# MCMP_Projeto_Final.net
KiCad netlist of a schematic drawn in EAGLE
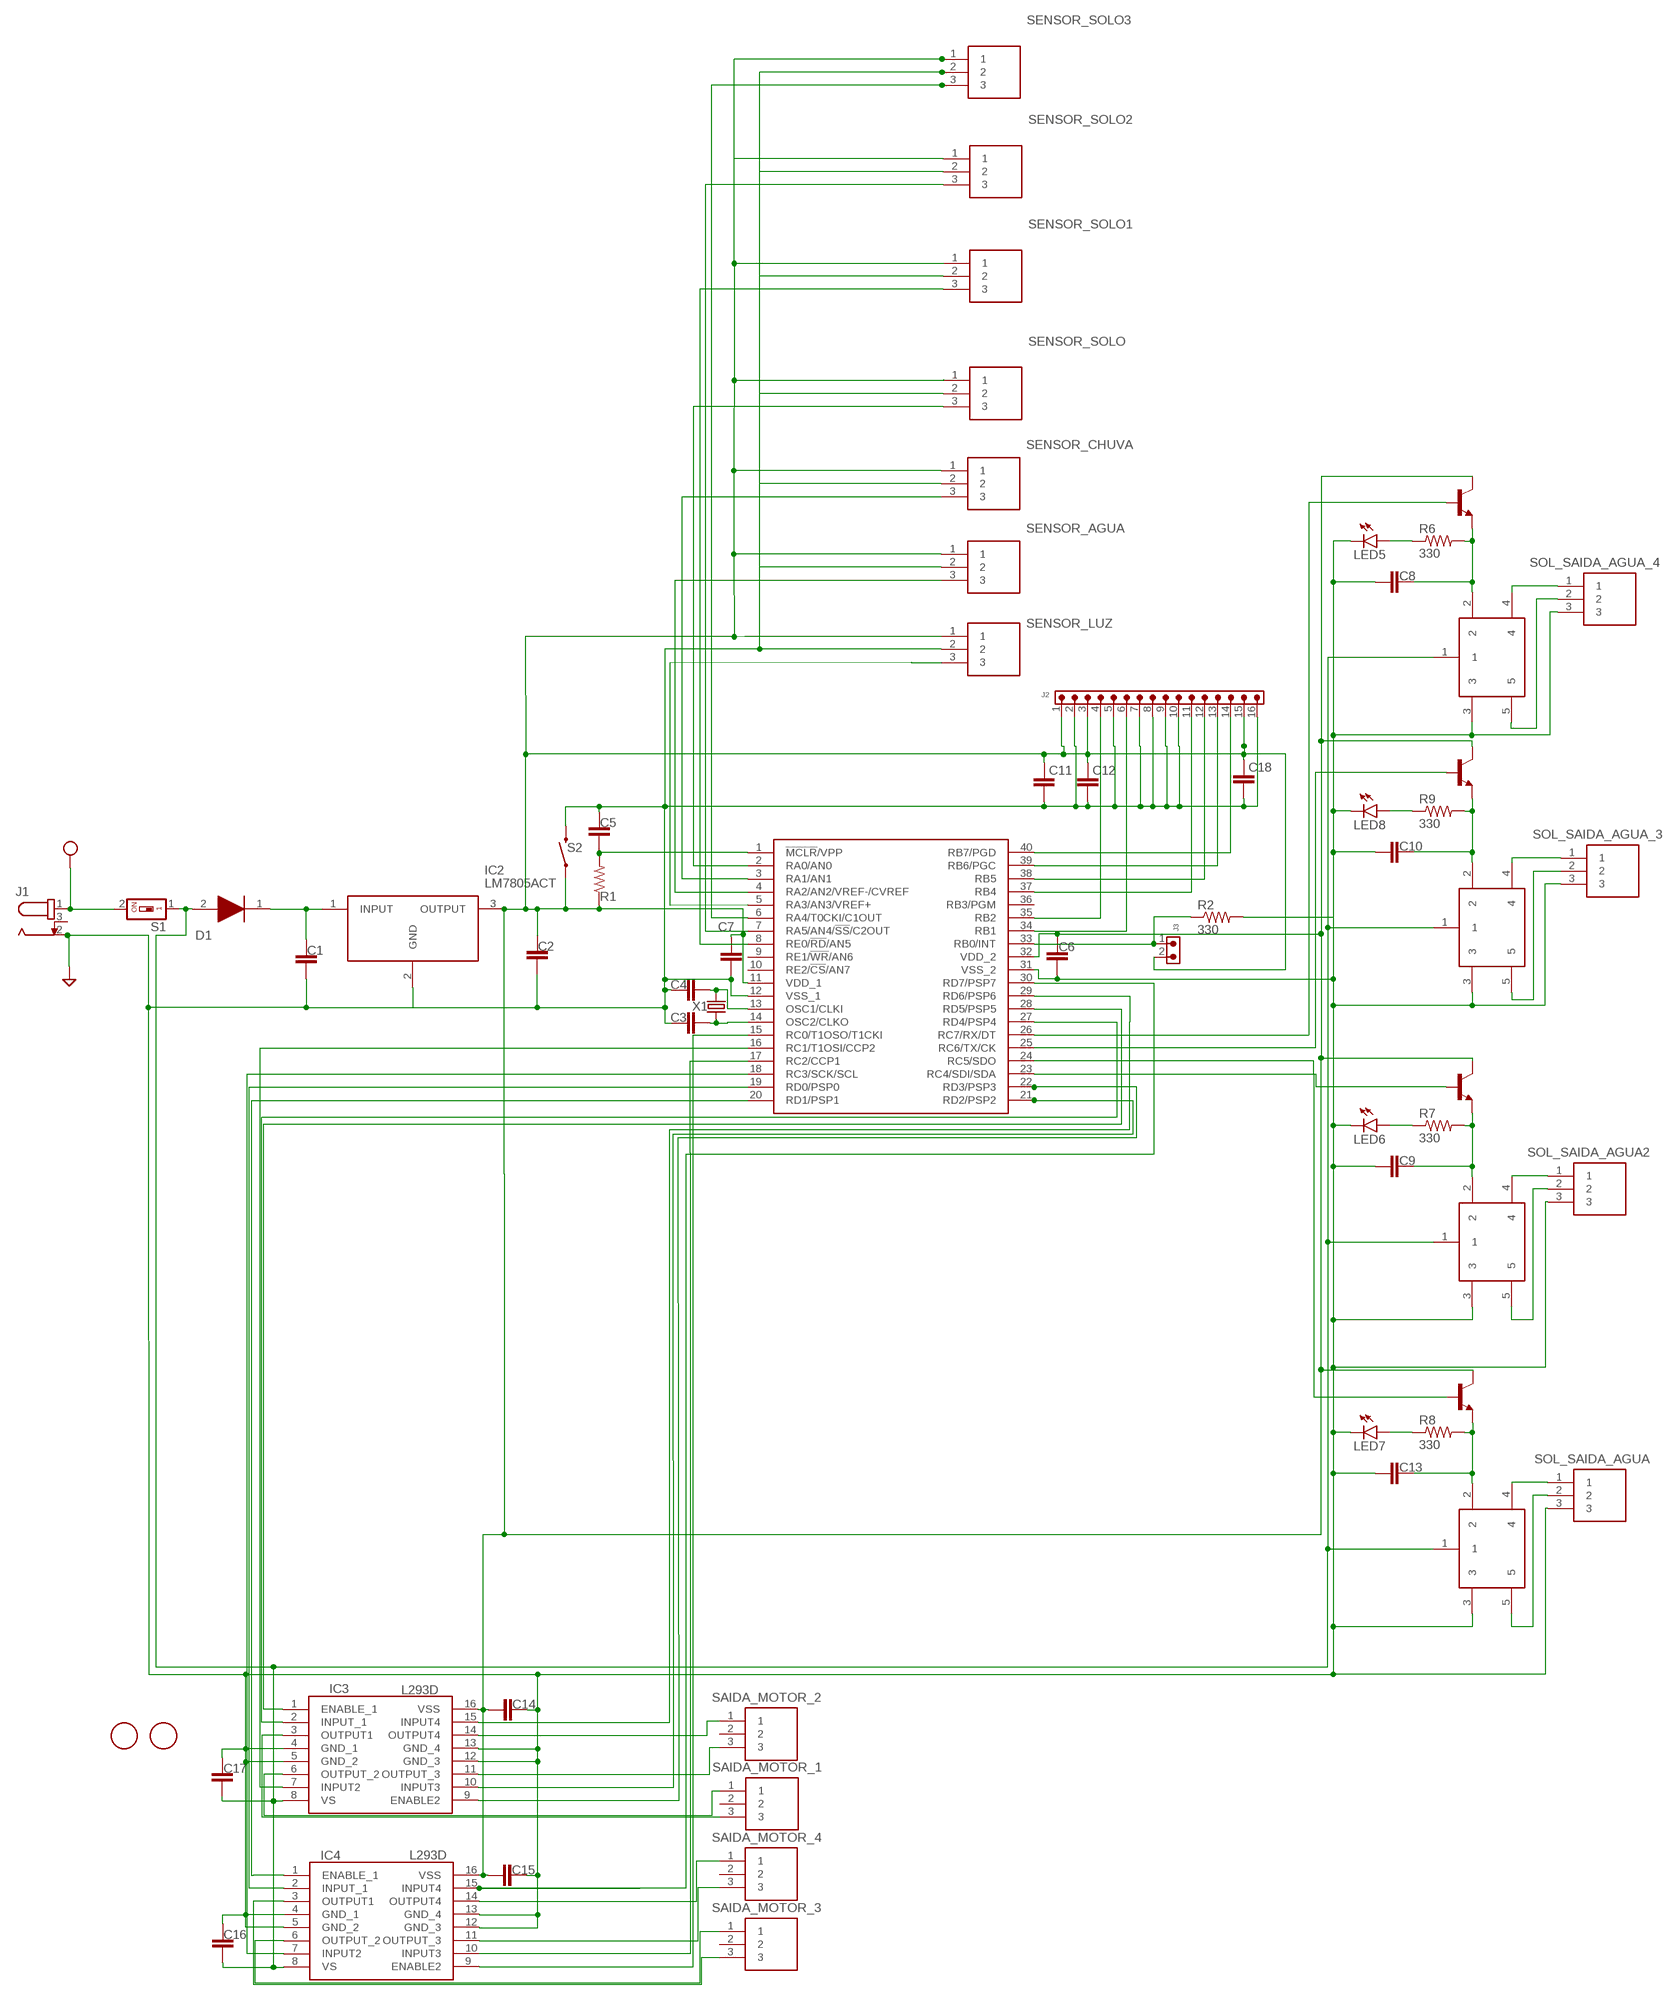
[diagram p0: schematic, sheet 1]

(export (version "E")
  (design (tool "Eeschema 10.0.6"))
  (components
    (comp (ref "C1")
      (value "470uF")
      (footprint "eagle-import:CAP_0805")
      (fields
        (field (name "DIGIKEY_PART_NUMBER") "311-1140-2-ND")
        (field (name "MANUFACTURER") "Yageo")
        (field (name "MPN") "CC0805KRX7R9BB104")
        (field (name "CREATED_BY") "PCBLayout.com")
      )
      (libsource (lib "eagle-import") (part "CC0805KRX7R9BB104"))
    )
    (comp (ref "C2")
      (value "1uF")
      (footprint "eagle-import:CAP_0805")
      (fields
        (field (name "DIGIKEY_PART_NUMBER") "311-1140-2-ND")
        (field (name "MANUFACTURER") "Yageo")
        (field (name "MPN") "CC0805KRX7R9BB104")
        (field (name "CREATED_BY") "PCBLayout.com")
      )
      (libsource (lib "eagle-import") (part "CC0805KRX7R9BB104"))
    )
    (comp (ref "C3")
      (value "33p")
      (footprint "eagle-import:CAP_0805")
      (fields
        (field (name "DIGIKEY_PART_NUMBER") "311-1140-2-ND")
        (field (name "MANUFACTURER") "Yageo")
        (field (name "MPN") "CC0805KRX7R9BB104")
        (field (name "CREATED_BY") "PCBLayout.com")
      )
      (libsource (lib "eagle-import") (part "CC0805KRX7R9BB104"))
    )
    (comp (ref "C4")
      (value "33p")
      (footprint "eagle-import:CAP_0805")
      (fields
        (field (name "DIGIKEY_PART_NUMBER") "311-1140-2-ND")
        (field (name "MANUFACTURER") "Yageo")
        (field (name "MPN") "CC0805KRX7R9BB104")
        (field (name "CREATED_BY") "PCBLayout.com")
      )
      (libsource (lib "eagle-import") (part "CC0805KRX7R9BB104"))
    )
    (comp (ref "C5")
      (value "10u")
      (footprint "eagle-import:CAP_0805")
      (fields
        (field (name "DIGIKEY_PART_NUMBER") "311-1140-2-ND")
        (field (name "MANUFACTURER") "Yageo")
        (field (name "MPN") "CC0805KRX7R9BB104")
        (field (name "CREATED_BY") "PCBLayout.com")
      )
      (libsource (lib "eagle-import") (part "CC0805KRX7R9BB104"))
    )
    (comp (ref "C6")
      (value "10u")
      (footprint "eagle-import:CAP_0805")
      (fields
        (field (name "DIGIKEY_PART_NUMBER") "311-1140-2-ND")
        (field (name "MANUFACTURER") "Yageo")
        (field (name "MPN") "CC0805KRX7R9BB104")
        (field (name "CREATED_BY") "PCBLayout.com")
      )
      (libsource (lib "eagle-import") (part "CC0805KRX7R9BB104"))
    )
    (comp (ref "C7")
      (value "10u")
      (footprint "eagle-import:CAP_0805")
      (fields
        (field (name "DIGIKEY_PART_NUMBER") "311-1140-2-ND")
        (field (name "MANUFACTURER") "Yageo")
        (field (name "MPN") "CC0805KRX7R9BB104")
        (field (name "CREATED_BY") "PCBLayout.com")
      )
      (libsource (lib "eagle-import") (part "CC0805KRX7R9BB104"))
    )
    (comp (ref "C8")
      (value "10u")
      (footprint "eagle-import:CAP_0805")
      (fields
        (field (name "DIGIKEY_PART_NUMBER") "311-1140-2-ND")
        (field (name "MANUFACTURER") "Yageo")
        (field (name "MPN") "CC0805KRX7R9BB104")
        (field (name "CREATED_BY") "PCBLayout.com")
      )
      (libsource (lib "eagle-import") (part "CC0805KRX7R9BB104"))
    )
    (comp (ref "C9")
      (value "10u")
      (footprint "eagle-import:CAP_0805")
      (fields
        (field (name "DIGIKEY_PART_NUMBER") "311-1140-2-ND")
        (field (name "MANUFACTURER") "Yageo")
        (field (name "MPN") "CC0805KRX7R9BB104")
        (field (name "CREATED_BY") "PCBLayout.com")
      )
      (libsource (lib "eagle-import") (part "CC0805KRX7R9BB104"))
    )
    (comp (ref "C10")
      (value "10u")
      (footprint "eagle-import:CAP_0805")
      (fields
        (field (name "DIGIKEY_PART_NUMBER") "311-1140-2-ND")
        (field (name "MANUFACTURER") "Yageo")
        (field (name "MPN") "CC0805KRX7R9BB104")
        (field (name "CREATED_BY") "PCBLayout.com")
      )
      (libsource (lib "eagle-import") (part "CC0805KRX7R9BB104"))
    )
    (comp (ref "C11")
      (value "10u")
      (footprint "eagle-import:CAP_0805")
      (fields
        (field (name "DIGIKEY_PART_NUMBER") "311-1140-2-ND")
        (field (name "MANUFACTURER") "Yageo")
        (field (name "MPN") "CC0805KRX7R9BB104")
        (field (name "CREATED_BY") "PCBLayout.com")
      )
      (libsource (lib "eagle-import") (part "CC0805KRX7R9BB104"))
    )
    (comp (ref "C12")
      (value "10u")
      (footprint "eagle-import:CAP_0805")
      (fields
        (field (name "DIGIKEY_PART_NUMBER") "311-1140-2-ND")
        (field (name "MANUFACTURER") "Yageo")
        (field (name "MPN") "CC0805KRX7R9BB104")
        (field (name "CREATED_BY") "PCBLayout.com")
      )
      (libsource (lib "eagle-import") (part "CC0805KRX7R9BB104"))
    )
    (comp (ref "C13")
      (value "10u")
      (footprint "eagle-import:CAP_0805")
      (fields
        (field (name "DIGIKEY_PART_NUMBER") "311-1140-2-ND")
        (field (name "MANUFACTURER") "Yageo")
        (field (name "MPN") "CC0805KRX7R9BB104")
        (field (name "CREATED_BY") "PCBLayout.com")
      )
      (libsource (lib "eagle-import") (part "CC0805KRX7R9BB104"))
    )
    (comp (ref "C14")
      (value "0.1u")
      (footprint "eagle-import:CAP_0805")
      (fields
        (field (name "DIGIKEY_PART_NUMBER") "311-1140-2-ND")
        (field (name "MANUFACTURER") "Yageo")
        (field (name "MPN") "CC0805KRX7R9BB104")
        (field (name "CREATED_BY") "PCBLayout.com")
      )
      (libsource (lib "eagle-import") (part "CC0805KRX7R9BB104"))
    )
    (comp (ref "C15")
      (value "0.1u")
      (footprint "eagle-import:CAP_0805")
      (fields
        (field (name "DIGIKEY_PART_NUMBER") "311-1140-2-ND")
        (field (name "MANUFACTURER") "Yageo")
        (field (name "MPN") "CC0805KRX7R9BB104")
        (field (name "CREATED_BY") "PCBLayout.com")
      )
      (libsource (lib "eagle-import") (part "CC0805KRX7R9BB104"))
    )
    (comp (ref "C16")
      (value "100u")
      (footprint "eagle-import:CAP_0805")
      (fields
        (field (name "DIGIKEY_PART_NUMBER") "311-1140-2-ND")
        (field (name "MANUFACTURER") "Yageo")
        (field (name "MPN") "CC0805KRX7R9BB104")
        (field (name "CREATED_BY") "PCBLayout.com")
      )
      (libsource (lib "eagle-import") (part "CC0805KRX7R9BB104"))
    )
    (comp (ref "C17")
      (value "100u")
      (footprint "eagle-import:CAP_0805")
      (fields
        (field (name "DIGIKEY_PART_NUMBER") "311-1140-2-ND")
        (field (name "MANUFACTURER") "Yageo")
        (field (name "MPN") "CC0805KRX7R9BB104")
        (field (name "CREATED_BY") "PCBLayout.com")
      )
      (libsource (lib "eagle-import") (part "CC0805KRX7R9BB104"))
    )
    (comp (ref "C18")
      (value "10u")
      (footprint "eagle-import:CAP_0805")
      (fields
        (field (name "DIGIKEY_PART_NUMBER") "311-1140-2-ND")
        (field (name "MANUFACTURER") "Yageo")
        (field (name "MPN") "CC0805KRX7R9BB104")
        (field (name "CREATED_BY") "PCBLayout.com")
      )
      (libsource (lib "eagle-import") (part "CC0805KRX7R9BB104"))
    )
    (comp (ref "D1")
      (value "1N4007S")
      (footprint "eagle-import:DIOAD1470W65L470D250")
      (fields (field (name "MOUSER_PART_NUMBER") "821-1N4007S"))
      (libsource (lib "eagle-import") (part "1N4007S"))
    )
    (comp (ref "IC1")
      (value "PIC16F877A-I_P")
      (footprint "eagle-import:DIP1550W56P254L5219H483Q40N")
      (fields
        (field (name "ARROW_PART_NUMBER") "PIC16F877A-I/P")
        (field (name "MOUSER_PART_NUMBER") "579-PIC16F877A-I/P")
      )
      (libsource (lib "eagle-import") (part "PIC16F877A-I_P"))
    )
    (comp (ref "IC2")
      (value "LM7805ACT")
      (footprint "eagle-import:TO254P470X1016X2019-3P")
      (fields (field (name "MOUSER_PART_NUMBER") "512-LM7805ACT"))
      (libsource (lib "eagle-import") (part "LM7805ACT"))
    )
    (comp (ref "IC3")
      (value "L293D")
      (footprint "eagle-import:DIP880W50P254L2000H510Q16N")
      (fields (field (name "MOUSER_PART_NUMBER") "511-L293D"))
      (libsource (lib "eagle-import") (part "L293D"))
    )
    (comp (ref "IC4")
      (value "L293D")
      (footprint "eagle-import:DIP880W50P254L2000H510Q16N")
      (fields (field (name "MOUSER_PART_NUMBER") "511-L293D"))
      (libsource (lib "eagle-import") (part "L293D"))
    )
    (comp (ref "J1")
      (value "694106301002")
      (footprint "eagle-import:694106301002")
      (fields
        (field (name "DIGIKEY_PART_NUMBER") "732-5930-ND")
        (field (name "MANUFACTURER") "Wurth Electronics Inc.")
        (field (name "CREATED_BY") "PCBLayout.com")
      )
      (libsource (lib "eagle-import") (part "694106301002"))
    )
    (comp (ref "J2")
      (value "6130XX11121_61301611121")
      (footprint "eagle-import:61301611121")
      (libsource (lib "eagle-import") (part "6130XX11121_61301611121"))
    )
    (comp (ref "J3")
      (value "6200XX11121_62000211121")
      (footprint "eagle-import:62000211121")
      (libsource (lib "eagle-import") (part "6200XX11121_62000211121"))
    )
    (comp (ref "K1")
      (value "SRD-05VDC-SL-C")
      (footprint "eagle-import:SRD")
      (libsource (lib "eagle-import") (part "SRD-05VDC-SL-C"))
    )
    (comp (ref "K2")
      (value "SRD-05VDC-SL-C")
      (footprint "eagle-import:SRD")
      (libsource (lib "eagle-import") (part "SRD-05VDC-SL-C"))
    )
    (comp (ref "K3")
      (value "SRD-05VDC-SL-C")
      (footprint "eagle-import:SRD")
      (libsource (lib "eagle-import") (part "SRD-05VDC-SL-C"))
    )
    (comp (ref "K5")
      (value "SRD-05VDC-SL-C")
      (footprint "eagle-import:SRD")
      (libsource (lib "eagle-import") (part "SRD-05VDC-SL-C"))
    )
    (comp (ref "LED5")
      (value "LEDCHIPLED_0805")
      (footprint "eagle-import:CHIPLED_0805")
      (libsource (lib "eagle-import") (part "LEDCHIPLED_0805"))
    )
    (comp (ref "LED6")
      (value "LEDCHIPLED_0805")
      (footprint "eagle-import:CHIPLED_0805")
      (libsource (lib "eagle-import") (part "LEDCHIPLED_0805"))
    )
    (comp (ref "LED7")
      (value "LEDCHIPLED_0805")
      (footprint "eagle-import:CHIPLED_0805")
      (libsource (lib "eagle-import") (part "LEDCHIPLED_0805"))
    )
    (comp (ref "LED8")
      (value "LEDCHIPLED_0805")
      (footprint "eagle-import:CHIPLED_0805")
      (libsource (lib "eagle-import") (part "LEDCHIPLED_0805"))
    )
    (comp (ref "Q1")
      (value "2N1711")
      (footprint "eagle-import:TO39")
      (libsource (lib "eagle-import") (part "2N1711"))
    )
    (comp (ref "Q2")
      (value "2N1711")
      (footprint "eagle-import:TO39")
      (libsource (lib "eagle-import") (part "2N1711"))
    )
    (comp (ref "Q3")
      (value "2N1711")
      (footprint "eagle-import:TO39")
      (libsource (lib "eagle-import") (part "2N1711"))
    )
    (comp (ref "Q5")
      (value "2N1711")
      (footprint "eagle-import:TO39")
      (libsource (lib "eagle-import") (part "2N1711"))
    )
    (comp (ref "R1")
      (value "10k")
      (footprint "eagle-import:RES_0805")
      (fields
        (field (name "DIGIKEY_PART_NUMBER") "541-0.0ATR-ND")
        (field (name "MANUFACTURER") "Vishay Dale")
        (field (name "MPN") "CRCW08050000Z0EA")
        (field (name "CREATED_BY") "PCBLayout.com")
      )
      (libsource (lib "eagle-import") (part "CRCW08050000Z0EA"))
    )
    (comp (ref "R2")
      (value "330")
      (footprint "eagle-import:RES_0805")
      (fields
        (field (name "DIGIKEY_PART_NUMBER") "541-0.0ATR-ND")
        (field (name "MANUFACTURER") "Vishay Dale")
        (field (name "MPN") "CRCW08050000Z0EA")
        (field (name "CREATED_BY") "PCBLayout.com")
      )
      (libsource (lib "eagle-import") (part "CRCW08050000Z0EA"))
    )
    (comp (ref "R6")
      (value "330")
      (footprint "eagle-import:RES_0805")
      (fields
        (field (name "DIGIKEY_PART_NUMBER") "541-0.0ATR-ND")
        (field (name "MANUFACTURER") "Vishay Dale")
        (field (name "MPN") "CRCW08050000Z0EA")
        (field (name "CREATED_BY") "PCBLayout.com")
      )
      (libsource (lib "eagle-import") (part "CRCW08050000Z0EA"))
    )
    (comp (ref "R7")
      (value "330")
      (footprint "eagle-import:RES_0805")
      (fields
        (field (name "DIGIKEY_PART_NUMBER") "541-0.0ATR-ND")
        (field (name "MANUFACTURER") "Vishay Dale")
        (field (name "MPN") "CRCW08050000Z0EA")
        (field (name "CREATED_BY") "PCBLayout.com")
      )
      (libsource (lib "eagle-import") (part "CRCW08050000Z0EA"))
    )
    (comp (ref "R8")
      (value "330")
      (footprint "eagle-import:RES_0805")
      (fields
        (field (name "DIGIKEY_PART_NUMBER") "541-0.0ATR-ND")
        (field (name "MANUFACTURER") "Vishay Dale")
        (field (name "MPN") "CRCW08050000Z0EA")
        (field (name "CREATED_BY") "PCBLayout.com")
      )
      (libsource (lib "eagle-import") (part "CRCW08050000Z0EA"))
    )
    (comp (ref "R9")
      (value "330")
      (footprint "eagle-import:RES_0805")
      (fields
        (field (name "DIGIKEY_PART_NUMBER") "541-0.0ATR-ND")
        (field (name "MANUFACTURER") "Vishay Dale")
        (field (name "MPN") "CRCW08050000Z0EA")
        (field (name "CREATED_BY") "PCBLayout.com")
      )
      (libsource (lib "eagle-import") (part "CRCW08050000Z0EA"))
    )
    (comp (ref "S1")
      (value "SWS001")
      (footprint "eagle-import:SMS-001")
      (libsource (lib "eagle-import") (part "SWS001"))
    )
    (comp (ref "S2")
      (value "MOMENTARY-SWITCH-SPST-PTH-6.0MM")
      (footprint "eagle-import:TACTILE_SWITCH_PTH_6.0MM")
      (libsource (lib "eagle-import") (part "MOMENTARY-SWITCH-SPST-PTH-6.0MM"))
    )
    (comp (ref "SAIDA_MOTOR_1")
      (value "TB005-762-03BE")
      (footprint "eagle-import:SHDR3W100P0X762_1X3_2286X1260X")
      (fields (field (name "MOUSER_PART_NUMBER") "490-TB005-762-03BE"))
      (libsource (lib "eagle-import") (part "TB005-762-03BE"))
    )
    (comp (ref "SAIDA_MOTOR_2")
      (value "TB005-762-03BE")
      (footprint "eagle-import:SHDR3W100P0X762_1X3_2286X1260X")
      (fields (field (name "MOUSER_PART_NUMBER") "490-TB005-762-03BE"))
      (libsource (lib "eagle-import") (part "TB005-762-03BE"))
    )
    (comp (ref "SAIDA_MOTOR_3")
      (value "TB005-762-03BE")
      (footprint "eagle-import:SHDR3W100P0X762_1X3_2286X1260X")
      (fields (field (name "MOUSER_PART_NUMBER") "490-TB005-762-03BE"))
      (libsource (lib "eagle-import") (part "TB005-762-03BE"))
    )
    (comp (ref "SAIDA_MOTOR_4")
      (value "TB005-762-03BE")
      (footprint "eagle-import:SHDR3W100P0X762_1X3_2286X1260X")
      (fields (field (name "MOUSER_PART_NUMBER") "490-TB005-762-03BE"))
      (libsource (lib "eagle-import") (part "TB005-762-03BE"))
    )
    (comp (ref "SENSOR_AGUA")
      (value "TB005-762-03BE")
      (footprint "eagle-import:SHDR3W100P0X762_1X3_2286X1260X")
      (fields (field (name "MOUSER_PART_NUMBER") "490-TB005-762-03BE"))
      (libsource (lib "eagle-import") (part "TB005-762-03BE"))
    )
    (comp (ref "SENSOR_CHUVA")
      (value "TB005-762-03BE")
      (footprint "eagle-import:SHDR3W100P0X762_1X3_2286X1260X")
      (fields (field (name "MOUSER_PART_NUMBER") "490-TB005-762-03BE"))
      (libsource (lib "eagle-import") (part "TB005-762-03BE"))
    )
    (comp (ref "SENSOR_LUZ")
      (value "TB005-762-03BE")
      (footprint "eagle-import:SHDR3W100P0X762_1X3_2286X1260X")
      (fields (field (name "MOUSER_PART_NUMBER") "490-TB005-762-03BE"))
      (libsource (lib "eagle-import") (part "TB005-762-03BE"))
    )
    (comp (ref "SENSOR_SOLO")
      (value "TB005-762-03BE")
      (footprint "eagle-import:SHDR3W100P0X762_1X3_2286X1260X")
      (fields (field (name "MOUSER_PART_NUMBER") "490-TB005-762-03BE"))
      (libsource (lib "eagle-import") (part "TB005-762-03BE"))
    )
    (comp (ref "SENSOR_SOLO1")
      (value "TB005-762-03BE")
      (footprint "eagle-import:SHDR3W100P0X762_1X3_2286X1260X")
      (fields (field (name "MOUSER_PART_NUMBER") "490-TB005-762-03BE"))
      (libsource (lib "eagle-import") (part "TB005-762-03BE"))
    )
    (comp (ref "SENSOR_SOLO2")
      (value "TB005-762-03BE")
      (footprint "eagle-import:SHDR3W100P0X762_1X3_2286X1260X")
      (fields (field (name "MOUSER_PART_NUMBER") "490-TB005-762-03BE"))
      (libsource (lib "eagle-import") (part "TB005-762-03BE"))
    )
    (comp (ref "SENSOR_SOLO3")
      (value "TB005-762-03BE")
      (footprint "eagle-import:SHDR3W100P0X762_1X3_2286X1260X")
      (fields (field (name "MOUSER_PART_NUMBER") "490-TB005-762-03BE"))
      (libsource (lib "eagle-import") (part "TB005-762-03BE"))
    )
    (comp (ref "SOL_SAIDA_AGUA")
      (value "TB005-762-03BE")
      (footprint "eagle-import:SHDR3W100P0X762_1X3_2286X1260X")
      (fields (field (name "MOUSER_PART_NUMBER") "490-TB005-762-03BE"))
      (libsource (lib "eagle-import") (part "TB005-762-03BE"))
    )
    (comp (ref "SOL_SAIDA_AGUA2")
      (value "TB005-762-03BE")
      (footprint "eagle-import:SHDR3W100P0X762_1X3_2286X1260X")
      (fields (field (name "MOUSER_PART_NUMBER") "490-TB005-762-03BE"))
      (libsource (lib "eagle-import") (part "TB005-762-03BE"))
    )
    (comp (ref "SOL_SAIDA_AGUA_3")
      (value "TB005-762-03BE")
      (footprint "eagle-import:SHDR3W100P0X762_1X3_2286X1260X")
      (fields (field (name "MOUSER_PART_NUMBER") "490-TB005-762-03BE"))
      (libsource (lib "eagle-import") (part "TB005-762-03BE"))
    )
    (comp (ref "SOL_SAIDA_AGUA_4")
      (value "TB005-762-03BE")
      (footprint "eagle-import:SHDR3W100P0X762_1X3_2286X1260X")
      (fields (field (name "MOUSER_PART_NUMBER") "490-TB005-762-03BE"))
      (libsource (lib "eagle-import") (part "TB005-762-03BE"))
    )
    (comp (ref "U$5")
      (value "FIDUCIAL")
      (footprint "eagle-import:FIDUCIAL_1MM")
      (libsource (lib "eagle-import") (part "FIDUCIAL"))
    )
    (comp (ref "U$6")
      (value "FIDUCIAL")
      (footprint "eagle-import:FIDUCIAL_1MM")
      (libsource (lib "eagle-import") (part "FIDUCIAL"))
    )
    (comp (ref "X1")
      (value "4Mhz")
      (footprint "eagle-import:5032_2P")
      (fields
        (field (name "MANUFACTURER") "Xinhunjing")
        (field (name "MPN") "5032/2P")
        (field (name "CREATED_BY") "PCBLayout.com")
      )
      (libsource (lib "eagle-import") (part "5032/2P"))
    )
  )
  (nets
    (net (code "1") (name "GND") (class "Default")
      (node (ref "C1") (pin "2") (pinfunction "2_2") (pintype "passive"))
      (node (ref "C10") (pin "2") (pinfunction "2_2") (pintype "passive"))
      (node (ref "C11") (pin "2") (pinfunction "2_2") (pintype "passive"))
      (node (ref "C12") (pin "2") (pinfunction "2_2") (pintype "passive"))
      (node (ref "C13") (pin "2") (pinfunction "2_2") (pintype "passive"))
      (node (ref "C14") (pin "2") (pinfunction "2_2") (pintype "passive"))
      (node (ref "C15") (pin "1") (pinfunction "1_1") (pintype "passive"))
      (node (ref "C16") (pin "1") (pinfunction "1_1") (pintype "passive"))
      (node (ref "C17") (pin "1") (pinfunction "1_1") (pintype "passive"))
      (node (ref "C18") (pin "2") (pinfunction "2_2") (pintype "passive"))
      (node (ref "C2") (pin "2") (pinfunction "2_2") (pintype "passive"))
      (node (ref "C3") (pin "1") (pinfunction "1_1") (pintype "passive"))
      (node (ref "C4") (pin "1") (pinfunction "1_1") (pintype "passive"))
      (node (ref "C5") (pin "1") (pinfunction "1_1") (pintype "passive"))
      (node (ref "C6") (pin "2") (pinfunction "2_2") (pintype "passive"))
      (node (ref "C7") (pin "2") (pinfunction "2_2") (pintype "passive"))
      (node (ref "C8") (pin "2") (pinfunction "2_2") (pintype "passive"))
      (node (ref "C9") (pin "2") (pinfunction "2_2") (pintype "passive"))
      (node (ref "IC1") (pin "12") (pinfunction "VSS_1_12") (pintype "bidirectional"))
      (node (ref "IC1") (pin "31") (pinfunction "VSS_2_31") (pintype "bidirectional"))
      (node (ref "IC2") (pin "2") (pinfunction "GND_2") (pintype "bidirectional"))
      (node (ref "IC3") (pin "12") (pinfunction "GND_3_12") (pintype "bidirectional"))
      (node (ref "IC3") (pin "13") (pinfunction "GND_4_13") (pintype "bidirectional"))
      (node (ref "IC3") (pin "4") (pinfunction "GND_1_4") (pintype "bidirectional"))
      (node (ref "IC3") (pin "5") (pinfunction "GND_2_5") (pintype "bidirectional"))
      (node (ref "IC4") (pin "12") (pinfunction "GND_3_12") (pintype "bidirectional"))
      (node (ref "IC4") (pin "13") (pinfunction "GND_4_13") (pintype "bidirectional"))
      (node (ref "IC4") (pin "4") (pinfunction "GND_1_4") (pintype "bidirectional"))
      (node (ref "IC4") (pin "5") (pinfunction "GND_2_5") (pintype "bidirectional"))
      (node (ref "J1") (pin "2") (pinfunction "2_2") (pintype "passive"))
      (node (ref "J2") (pin "10") (pinfunction "10_10") (pintype "passive"))
      (node (ref "J2") (pin "16") (pinfunction "16_16") (pintype "passive"))
      (node (ref "J2") (pin "2") (pinfunction "2_2") (pintype "passive"))
      (node (ref "J2") (pin "5") (pinfunction "5_5") (pintype "passive"))
      (node (ref "J2") (pin "7") (pinfunction "7_7") (pintype "passive"))
      (node (ref "J2") (pin "8") (pinfunction "8_8") (pintype "passive"))
      (node (ref "J2") (pin "9") (pinfunction "9_9") (pintype "passive"))
      (node (ref "K1") (pin "3") (pinfunction "3_3") (pintype "bidirectional"))
      (node (ref "K2") (pin "3") (pinfunction "3_3") (pintype "bidirectional"))
      (node (ref "K3") (pin "3") (pinfunction "3_3") (pintype "bidirectional"))
      (node (ref "K5") (pin "3") (pinfunction "3_3") (pintype "bidirectional"))
      (node (ref "LED5") (pin "C") (pinfunction "C_C") (pintype "passive"))
      (node (ref "LED6") (pin "C") (pinfunction "C_C") (pintype "passive"))
      (node (ref "LED7") (pin "C") (pinfunction "C_C") (pintype "passive"))
      (node (ref "LED8") (pin "C") (pinfunction "C_C") (pintype "passive"))
      (node (ref "R2") (pin "2") (pinfunction "2_2") (pintype "passive"))
      (node (ref "S2") (pin "3") (pinfunction "2_3") (pintype "passive"))
      (node (ref "SENSOR_AGUA") (pin "2") (pinfunction "2_2") (pintype "bidirectional"))
      (node (ref "SENSOR_CHUVA") (pin "2") (pinfunction "2_2") (pintype "bidirectional"))
      (node (ref "SENSOR_LUZ") (pin "2") (pinfunction "2_2") (pintype "bidirectional"))
      (node (ref "SENSOR_SOLO") (pin "2") (pinfunction "2_2") (pintype "bidirectional"))
      (node (ref "SENSOR_SOLO1") (pin "2") (pinfunction "2_2") (pintype "bidirectional"))
      (node (ref "SENSOR_SOLO2") (pin "2") (pinfunction "2_2") (pintype "bidirectional"))
      (node (ref "SENSOR_SOLO3") (pin "2") (pinfunction "2_2") (pintype "bidirectional"))
      (node (ref "SOL_SAIDA_AGUA") (pin "3") (pinfunction "3_3") (pintype "bidirectional"))
      (node (ref "SOL_SAIDA_AGUA2") (pin "3") (pinfunction "3_3") (pintype "bidirectional"))
      (node (ref "SOL_SAIDA_AGUA_3") (pin "3") (pinfunction "3_3") (pintype "bidirectional"))
      (node (ref "SOL_SAIDA_AGUA_4") (pin "3") (pinfunction "3_3") (pintype "bidirectional"))
    )
    (net (code "2") (name "Net-(D1-A)") (class "Default")
      (node (ref "C16") (pin "2") (pinfunction "2_2") (pintype "passive"))
      (node (ref "C17") (pin "2") (pinfunction "2_2") (pintype "passive"))
      (node (ref "D1") (pin "2") (pinfunction "A_2") (pintype "bidirectional"))
      (node (ref "IC3") (pin "8") (pinfunction "VS_8") (pintype "bidirectional"))
      (node (ref "IC4") (pin "8") (pinfunction "VS_8") (pintype "bidirectional"))
      (node (ref "K1") (pin "1") (pinfunction "1_1") (pintype "bidirectional"))
      (node (ref "K2") (pin "1") (pinfunction "1_1") (pintype "bidirectional"))
      (node (ref "K3") (pin "1") (pinfunction "1_1") (pintype "bidirectional"))
      (node (ref "K5") (pin "1") (pinfunction "1_1") (pintype "bidirectional"))
      (node (ref "S1") (pin "1") (pinfunction "1_1") (pintype "passive"))
    )
    (net (code "3") (name "Net-(D1-K)") (class "Default")
      (node (ref "C1") (pin "1") (pinfunction "1_1") (pintype "passive"))
      (node (ref "D1") (pin "1") (pinfunction "K_1") (pintype "bidirectional"))
      (node (ref "IC2") (pin "1") (pinfunction "INPUT_1") (pintype "bidirectional"))
    )
    (net (code "4") (name "Net-(IC1-OSC1{slash}CLKI)") (class "Default")
      (node (ref "C4") (pin "2") (pinfunction "2_2") (pintype "passive"))
      (node (ref "IC1") (pin "13") (pinfunction "OSC1/CLKI_13") (pintype "bidirectional"))
      (node (ref "X1") (pin "2") (pinfunction "2_2") (pintype "passive"))
    )
    (net (code "5") (name "Net-(IC1-OSC2{slash}CLKO)") (class "Default")
      (node (ref "C3") (pin "2") (pinfunction "2_2") (pintype "passive"))
      (node (ref "IC1") (pin "14") (pinfunction "OSC2/CLKO_14") (pintype "bidirectional"))
      (node (ref "X1") (pin "1") (pinfunction "1_1") (pintype "passive"))
    )
    (net (code "6") (name "Net-(IC1-RA0{slash}AN0)") (class "Default")
      (node (ref "IC1") (pin "2") (pinfunction "RA0/AN0_2") (pintype "bidirectional"))
      (node (ref "SENSOR_SOLO") (pin "3") (pinfunction "3_3") (pintype "bidirectional"))
    )
    (net (code "7") (name "Net-(IC1-RA1{slash}AN1)") (class "Default")
      (node (ref "IC1") (pin "3") (pinfunction "RA1/AN1_3") (pintype "bidirectional"))
      (node (ref "SENSOR_CHUVA") (pin "3") (pinfunction "3_3") (pintype "bidirectional"))
    )
    (net (code "8") (name "Net-(IC1-RA2{slash}AN2{slash}VREF-{slash}CVREF)") (class "Default")
      (node (ref "IC1") (pin "4") (pinfunction "RA2/AN2/VREF-/CVREF_4") (pintype "bidirectional"))
      (node (ref "SENSOR_AGUA") (pin "3") (pinfunction "3_3") (pintype "bidirectional"))
    )
    (net (code "9") (name "Net-(IC1-RA3{slash}AN3{slash}VREF+)") (class "Default")
      (node (ref "IC1") (pin "5") (pinfunction "RA3/AN3/VREF+_5") (pintype "bidirectional"))
      (node (ref "SENSOR_LUZ") (pin "3") (pinfunction "3_3") (pintype "bidirectional"))
    )
    (net (code "10") (name "Net-(IC1-RA4{slash}T0CKI{slash}C1OUT)") (class "Default")
      (node (ref "IC1") (pin "6") (pinfunction "RA4/T0CKI/C1OUT_6") (pintype "bidirectional"))
      (node (ref "SENSOR_SOLO3") (pin "3") (pinfunction "3_3") (pintype "bidirectional"))
    )
    (net (code "11") (name "Net-(IC1-RA5{slash}AN4{slash}~{SS}{slash}C2OUT)") (class "Default")
      (node (ref "IC1") (pin "7") (pinfunction "RA5/AN4/~{SS}/C2OUT_7") (pintype "bidirectional"))
      (node (ref "SENSOR_SOLO2") (pin "3") (pinfunction "3_3") (pintype "bidirectional"))
    )
    (net (code "12") (name "Net-(IC1-RB0{slash}INT)") (class "Default")
      (node (ref "IC1") (pin "33") (pinfunction "RB0/INT_33") (pintype "bidirectional"))
      (node (ref "J3") (pin "1") (pinfunction "1_1") (pintype "passive"))
      (node (ref "R2") (pin "1") (pinfunction "1_1") (pintype "passive"))
    )
    (net (code "13") (name "Net-(IC1-RB1)") (class "Default")
      (node (ref "IC1") (pin "34") (pinfunction "RB1_34") (pintype "bidirectional"))
      (node (ref "J2") (pin "6") (pinfunction "6_6") (pintype "passive"))
    )
    (net (code "14") (name "Net-(IC1-RB2)") (class "Default")
      (node (ref "IC1") (pin "35") (pinfunction "RB2_35") (pintype "bidirectional"))
      (node (ref "J2") (pin "4") (pinfunction "4_4") (pintype "passive"))
    )
    (net (code "15") (name "Net-(IC1-RB4)") (class "Default")
      (node (ref "IC1") (pin "37") (pinfunction "RB4_37") (pintype "bidirectional"))
      (node (ref "J2") (pin "11") (pinfunction "11_11") (pintype "passive"))
    )
    (net (code "16") (name "Net-(IC1-RB5)") (class "Default")
      (node (ref "IC1") (pin "38") (pinfunction "RB5_38") (pintype "bidirectional"))
      (node (ref "J2") (pin "12") (pinfunction "12_12") (pintype "passive"))
    )
    (net (code "17") (name "Net-(IC1-RB6{slash}PGC)") (class "Default")
      (node (ref "IC1") (pin "39") (pinfunction "RB6/PGC_39") (pintype "bidirectional"))
      (node (ref "J2") (pin "13") (pinfunction "13_13") (pintype "passive"))
    )
    (net (code "18") (name "Net-(IC1-RB7{slash}PGD)") (class "Default")
      (node (ref "IC1") (pin "40") (pinfunction "RB7/PGD_40") (pintype "bidirectional"))
      (node (ref "J2") (pin "14") (pinfunction "14_14") (pintype "passive"))
    )
    (net (code "19") (name "Net-(IC1-RC0{slash}T1OSO{slash}T1CKI)") (class "Default")
      (node (ref "IC1") (pin "15") (pinfunction "RC0/T1OSO/T1CKI_15") (pintype "bidirectional"))
      (node (ref "IC4") (pin "9") (pinfunction "ENABLE2_9") (pintype "bidirectional"))
    )
    (net (code "20") (name "Net-(IC1-RC1{slash}T1OSI{slash}CCP2)") (class "Default")
      (node (ref "IC1") (pin "16") (pinfunction "RC1/T1OSI/CCP2_16") (pintype "bidirectional"))
      (node (ref "IC3") (pin "7") (pinfunction "INPUT2_7") (pintype "bidirectional"))
    )
    (net (code "21") (name "Net-(IC1-RC2{slash}CCP1)") (class "Default")
      (node (ref "IC1") (pin "17") (pinfunction "RC2/CCP1_17") (pintype "bidirectional"))
      (node (ref "IC4") (pin "10") (pinfunction "INPUT3_10") (pintype "bidirectional"))
    )
    (net (code "22") (name "Net-(IC1-RC3{slash}SCK{slash}SCL)") (class "Default")
      (node (ref "IC1") (pin "18") (pinfunction "RC3/SCK/SCL_18") (pintype "bidirectional"))
      (node (ref "IC4") (pin "7") (pinfunction "INPUT2_7") (pintype "bidirectional"))
    )
    (net (code "23") (name "Net-(IC1-RC4{slash}SDI{slash}SDA)") (class "Default")
      (node (ref "IC1") (pin "23") (pinfunction "RC4/SDI/SDA_23") (pintype "bidirectional"))
      (node (ref "Q2") (pin "2") (pinfunction "B_2") (pintype "passive"))
    )
    (net (code "24") (name "Net-(IC1-RC5{slash}SDO)") (class "Default")
      (node (ref "IC1") (pin "24") (pinfunction "RC5/SDO_24") (pintype "bidirectional"))
      (node (ref "Q5") (pin "2") (pinfunction "B_2") (pintype "passive"))
    )
    (net (code "25") (name "Net-(IC1-RC6{slash}TX{slash}CK)") (class "Default")
      (node (ref "IC1") (pin "25") (pinfunction "RC6/TX/CK_25") (pintype "bidirectional"))
      (node (ref "Q3") (pin "2") (pinfunction "B_2") (pintype "passive"))
    )
    (net (code "26") (name "Net-(IC1-RC7{slash}RX{slash}DT)") (class "Default")
      (node (ref "IC1") (pin "26") (pinfunction "RC7/RX/DT_26") (pintype "bidirectional"))
      (node (ref "Q1") (pin "2") (pinfunction "B_2") (pintype "passive"))
    )
    (net (code "27") (name "Net-(IC1-RD0{slash}PSP0)") (class "Default")
      (node (ref "IC1") (pin "19") (pinfunction "RD0/PSP0_19") (pintype "bidirectional"))
      (node (ref "IC4") (pin "2") (pinfunction "INPUT_1_2") (pintype "bidirectional"))
    )
    (net (code "28") (name "Net-(IC1-RD1{slash}PSP1)") (class "Default")
      (node (ref "IC1") (pin "20") (pinfunction "RD1/PSP1_20") (pintype "bidirectional"))
      (node (ref "IC4") (pin "1") (pinfunction "ENABLE_1_1") (pintype "bidirectional"))
    )
    (net (code "29") (name "Net-(IC1-RD2{slash}PSP2)") (class "Default")
      (node (ref "IC1") (pin "21") (pinfunction "RD2/PSP2_21") (pintype "bidirectional"))
      (node (ref "IC3") (pin "10") (pinfunction "INPUT3_10") (pintype "bidirectional"))
    )
    (net (code "30") (name "Net-(IC1-RD3{slash}PSP3)") (class "Default")
      (node (ref "IC1") (pin "22") (pinfunction "RD3/PSP3_22") (pintype "bidirectional"))
      (node (ref "IC3") (pin "9") (pinfunction "ENABLE2_9") (pintype "bidirectional"))
    )
    (net (code "31") (name "Net-(IC1-RD4{slash}PSP4)") (class "Default")
      (node (ref "IC1") (pin "27") (pinfunction "RD4/PSP4_27") (pintype "bidirectional"))
      (node (ref "IC3") (pin "2") (pinfunction "INPUT_1_2") (pintype "bidirectional"))
    )
    (net (code "32") (name "Net-(IC1-RD5{slash}PSP5)") (class "Default")
      (node (ref "IC1") (pin "28") (pinfunction "RD5/PSP5_28") (pintype "bidirectional"))
      (node (ref "IC3") (pin "1") (pinfunction "ENABLE_1_1") (pintype "bidirectional"))
    )
    (net (code "33") (name "Net-(IC1-RD6{slash}PSP6)") (class "Default")
      (node (ref "IC1") (pin "29") (pinfunction "RD6/PSP6_29") (pintype "bidirectional"))
      (node (ref "IC3") (pin "15") (pinfunction "INPUT4_15") (pintype "bidirectional"))
    )
    (net (code "34") (name "Net-(IC1-RD7{slash}PSP7)") (class "Default")
      (node (ref "IC1") (pin "30") (pinfunction "RD7/PSP7_30") (pintype "bidirectional"))
      (node (ref "IC4") (pin "15") (pinfunction "INPUT4_15") (pintype "bidirectional"))
    )
    (net (code "35") (name "Net-(IC1-RE0{slash}~{RD}{slash}AN5)") (class "Default")
      (node (ref "IC1") (pin "8") (pinfunction "RE0/~{RD}/AN5_8") (pintype "bidirectional"))
      (node (ref "SENSOR_SOLO1") (pin "3") (pinfunction "3_3") (pintype "bidirectional"))
    )
    (net (code "36") (name "Net-(IC1-VDD_1)") (class "Default")
      (node (ref "C11") (pin "1") (pinfunction "1_1") (pintype "passive"))
      (node (ref "C12") (pin "1") (pinfunction "1_1") (pintype "passive"))
      (node (ref "C14") (pin "1") (pinfunction "1_1") (pintype "passive"))
      (node (ref "C15") (pin "2") (pinfunction "2_2") (pintype "passive"))
      (node (ref "C18") (pin "1") (pinfunction "1_1") (pintype "passive"))
      (node (ref "C2") (pin "1") (pinfunction "1_1") (pintype "passive"))
      (node (ref "C6") (pin "1") (pinfunction "1_1") (pintype "passive"))
      (node (ref "C7") (pin "1") (pinfunction "1_1") (pintype "passive"))
      (node (ref "IC1") (pin "11") (pinfunction "VDD_1_11") (pintype "bidirectional"))
      (node (ref "IC1") (pin "32") (pinfunction "VDD_2_32") (pintype "bidirectional"))
      (node (ref "IC2") (pin "3") (pinfunction "OUTPUT_3") (pintype "bidirectional"))
      (node (ref "IC3") (pin "16") (pinfunction "VSS_16") (pintype "bidirectional"))
      (node (ref "IC4") (pin "16") (pinfunction "VSS_16") (pintype "bidirectional"))
      (node (ref "J2") (pin "1") (pinfunction "1_1") (pintype "passive"))
      (node (ref "J2") (pin "15") (pinfunction "15_15") (pintype "passive"))
      (node (ref "J2") (pin "3") (pinfunction "3_3") (pintype "passive"))
      (node (ref "J3") (pin "2") (pinfunction "2_2") (pintype "passive"))
      (node (ref "Q1") (pin "3") (pinfunction "C_3") (pintype "passive"))
      (node (ref "Q2") (pin "3") (pinfunction "C_3") (pintype "passive"))
      (node (ref "Q3") (pin "3") (pinfunction "C_3") (pintype "passive"))
      (node (ref "Q5") (pin "3") (pinfunction "C_3") (pintype "passive"))
      (node (ref "R1") (pin "1") (pinfunction "1_1") (pintype "passive"))
      (node (ref "S2") (pin "1") (pinfunction "1_1") (pintype "passive"))
      (node (ref "SENSOR_AGUA") (pin "1") (pinfunction "1_1") (pintype "bidirectional"))
      (node (ref "SENSOR_CHUVA") (pin "1") (pinfunction "1_1") (pintype "bidirectional"))
      (node (ref "SENSOR_LUZ") (pin "1") (pinfunction "1_1") (pintype "bidirectional"))
      (node (ref "SENSOR_SOLO") (pin "1") (pinfunction "1_1") (pintype "bidirectional"))
      (node (ref "SENSOR_SOLO1") (pin "1") (pinfunction "1_1") (pintype "bidirectional"))
      (node (ref "SENSOR_SOLO2") (pin "1") (pinfunction "1_1") (pintype "bidirectional"))
      (node (ref "SENSOR_SOLO3") (pin "1") (pinfunction "1_1") (pintype "bidirectional"))
    )
    (net (code "37") (name "Net-(IC1-~{MCLR}{slash}VPP)") (class "Default")
      (node (ref "C5") (pin "2") (pinfunction "2_2") (pintype "passive"))
      (node (ref "IC1") (pin "1") (pinfunction "~{MCLR}/VPP_1") (pintype "bidirectional"))
      (node (ref "R1") (pin "2") (pinfunction "2_2") (pintype "passive"))
    )
    (net (code "38") (name "Net-(IC3-OUTPUT1)") (class "Default")
      (node (ref "IC3") (pin "3") (pinfunction "OUTPUT1_3") (pintype "bidirectional"))
      (node (ref "SAIDA_MOTOR_1") (pin "3") (pinfunction "3_3") (pintype "bidirectional"))
    )
    (net (code "39") (name "Net-(IC3-OUTPUT4)") (class "Default")
      (node (ref "IC3") (pin "14") (pinfunction "OUTPUT4_14") (pintype "bidirectional"))
      (node (ref "SAIDA_MOTOR_2") (pin "1") (pinfunction "1_1") (pintype "bidirectional"))
    )
    (net (code "40") (name "Net-(IC3-OUTPUT_2)") (class "Default")
      (node (ref "IC3") (pin "6") (pinfunction "OUTPUT_2_6") (pintype "bidirectional"))
      (node (ref "SAIDA_MOTOR_1") (pin "1") (pinfunction "1_1") (pintype "bidirectional"))
    )
    (net (code "41") (name "Net-(IC3-OUTPUT_3)") (class "Default")
      (node (ref "IC3") (pin "11") (pinfunction "OUTPUT_3_11") (pintype "bidirectional"))
      (node (ref "SAIDA_MOTOR_2") (pin "3") (pinfunction "3_3") (pintype "bidirectional"))
    )
    (net (code "42") (name "Net-(IC4-OUTPUT1)") (class "Default")
      (node (ref "IC4") (pin "3") (pinfunction "OUTPUT1_3") (pintype "bidirectional"))
      (node (ref "SAIDA_MOTOR_3") (pin "3") (pinfunction "3_3") (pintype "bidirectional"))
    )
    (net (code "43") (name "Net-(IC4-OUTPUT4)") (class "Default")
      (node (ref "IC4") (pin "14") (pinfunction "OUTPUT4_14") (pintype "bidirectional"))
      (node (ref "SAIDA_MOTOR_4") (pin "1") (pinfunction "1_1") (pintype "bidirectional"))
    )
    (net (code "44") (name "Net-(IC4-OUTPUT_2)") (class "Default")
      (node (ref "IC4") (pin "6") (pinfunction "OUTPUT_2_6") (pintype "bidirectional"))
      (node (ref "SAIDA_MOTOR_3") (pin "1") (pinfunction "1_1") (pintype "bidirectional"))
    )
    (net (code "45") (name "Net-(IC4-OUTPUT_3)") (class "Default")
      (node (ref "IC4") (pin "11") (pinfunction "OUTPUT_3_11") (pintype "bidirectional"))
      (node (ref "SAIDA_MOTOR_4") (pin "3") (pinfunction "3_3") (pintype "bidirectional"))
    )
    (net (code "46") (name "Net-(K1-Pad4)") (class "Default")
      (node (ref "K1") (pin "4") (pinfunction "4_4") (pintype "bidirectional"))
      (node (ref "SOL_SAIDA_AGUA_4") (pin "1") (pinfunction "1_1") (pintype "bidirectional"))
    )
    (net (code "47") (name "Net-(K1-Pad5)") (class "Default")
      (node (ref "K1") (pin "5") (pinfunction "5_5") (pintype "bidirectional"))
      (node (ref "SOL_SAIDA_AGUA_4") (pin "2") (pinfunction "2_2") (pintype "bidirectional"))
    )
    (net (code "48") (name "Net-(K2-Pad4)") (class "Default")
      (node (ref "K2") (pin "4") (pinfunction "4_4") (pintype "bidirectional"))
      (node (ref "SOL_SAIDA_AGUA2") (pin "1") (pinfunction "1_1") (pintype "bidirectional"))
    )
    (net (code "49") (name "Net-(K2-Pad5)") (class "Default")
      (node (ref "K2") (pin "5") (pinfunction "5_5") (pintype "bidirectional"))
      (node (ref "SOL_SAIDA_AGUA2") (pin "2") (pinfunction "2_2") (pintype "bidirectional"))
    )
    (net (code "50") (name "Net-(K3-Pad4)") (class "Default")
      (node (ref "K3") (pin "4") (pinfunction "4_4") (pintype "bidirectional"))
      (node (ref "SOL_SAIDA_AGUA_3") (pin "1") (pinfunction "1_1") (pintype "bidirectional"))
    )
    (net (code "51") (name "Net-(K3-Pad5)") (class "Default")
      (node (ref "K3") (pin "5") (pinfunction "5_5") (pintype "bidirectional"))
      (node (ref "SOL_SAIDA_AGUA_3") (pin "2") (pinfunction "2_2") (pintype "bidirectional"))
    )
    (net (code "52") (name "Net-(K5-Pad4)") (class "Default")
      (node (ref "K5") (pin "4") (pinfunction "4_4") (pintype "bidirectional"))
      (node (ref "SOL_SAIDA_AGUA") (pin "1") (pinfunction "1_1") (pintype "bidirectional"))
    )
    (net (code "53") (name "Net-(K5-Pad5)") (class "Default")
      (node (ref "K5") (pin "5") (pinfunction "5_5") (pintype "bidirectional"))
      (node (ref "SOL_SAIDA_AGUA") (pin "2") (pinfunction "2_2") (pintype "bidirectional"))
    )
    (net (code "54") (name "Net-(LED5-PadA)") (class "Default")
      (node (ref "LED5") (pin "A") (pinfunction "A_A") (pintype "passive"))
      (node (ref "R6") (pin "1") (pinfunction "1_1") (pintype "passive"))
    )
    (net (code "55") (name "Net-(LED6-PadA)") (class "Default")
      (node (ref "LED6") (pin "A") (pinfunction "A_A") (pintype "passive"))
      (node (ref "R7") (pin "1") (pinfunction "1_1") (pintype "passive"))
    )
    (net (code "56") (name "Net-(LED7-PadA)") (class "Default")
      (node (ref "LED7") (pin "A") (pinfunction "A_A") (pintype "passive"))
      (node (ref "R8") (pin "1") (pinfunction "1_1") (pintype "passive"))
    )
    (net (code "57") (name "Net-(LED8-PadA)") (class "Default")
      (node (ref "LED8") (pin "A") (pinfunction "A_A") (pintype "passive"))
      (node (ref "R9") (pin "1") (pinfunction "1_1") (pintype "passive"))
    )
    (net (code "58") (name "Net-(Q1-E)") (class "Default")
      (node (ref "C8") (pin "1") (pinfunction "1_1") (pintype "passive"))
      (node (ref "K1") (pin "2") (pinfunction "2_2") (pintype "bidirectional"))
      (node (ref "Q1") (pin "1") (pinfunction "E_1") (pintype "passive"))
      (node (ref "R6") (pin "2") (pinfunction "2_2") (pintype "passive"))
    )
    (net (code "59") (name "Net-(Q2-E)") (class "Default")
      (node (ref "C9") (pin "1") (pinfunction "1_1") (pintype "passive"))
      (node (ref "K2") (pin "2") (pinfunction "2_2") (pintype "bidirectional"))
      (node (ref "Q2") (pin "1") (pinfunction "E_1") (pintype "passive"))
      (node (ref "R7") (pin "2") (pinfunction "2_2") (pintype "passive"))
    )
    (net (code "60") (name "Net-(Q3-E)") (class "Default")
      (node (ref "C10") (pin "1") (pinfunction "1_1") (pintype "passive"))
      (node (ref "K3") (pin "2") (pinfunction "2_2") (pintype "bidirectional"))
      (node (ref "Q3") (pin "1") (pinfunction "E_1") (pintype "passive"))
      (node (ref "R9") (pin "2") (pinfunction "2_2") (pintype "passive"))
    )
    (net (code "61") (name "Net-(Q5-E)") (class "Default")
      (node (ref "C13") (pin "1") (pinfunction "1_1") (pintype "passive"))
      (node (ref "K5") (pin "2") (pinfunction "2_2") (pintype "bidirectional"))
      (node (ref "Q5") (pin "1") (pinfunction "E_1") (pintype "passive"))
      (node (ref "R8") (pin "2") (pinfunction "2_2") (pintype "passive"))
    )
    (net (code "62") (name "VCC-CIRCLE") (class "Default")
      (node (ref "J1") (pin "1") (pinfunction "1_1") (pintype "passive"))
      (node (ref "S1") (pin "2") (pinfunction "2_2") (pintype "passive"))
    )
    (net (code "63") (name "unconnected-(IC1-RB3{slash}PGM-Pad36)") (class "Default")
      (node (ref "IC1") (pin "36") (pinfunction "RB3/PGM_36") (pintype "bidirectional"))
    )
    (net (code "64") (name "unconnected-(IC1-RE1{slash}~{WR}{slash}AN6-Pad9)") (class "Default")
      (node (ref "IC1") (pin "9") (pinfunction "RE1/~{WR}/AN6_9") (pintype "bidirectional"))
    )
    (net (code "65") (name "unconnected-(IC1-RE2{slash}~{CS}{slash}AN7-Pad10)") (class "Default")
      (node (ref "IC1") (pin "10") (pinfunction "RE2/~{CS}/AN7_10") (pintype "bidirectional"))
    )
    (net (code "66") (name "unconnected-(J1-Pad3)") (class "Default")
      (node (ref "J1") (pin "3") (pinfunction "3_3") (pintype "passive"))
    )
    (net (code "67") (name "unconnected-(SAIDA_MOTOR_1-Pad2)") (class "Default")
      (node (ref "SAIDA_MOTOR_1") (pin "2") (pinfunction "2_2") (pintype "bidirectional"))
    )
    (net (code "68") (name "unconnected-(SAIDA_MOTOR_2-Pad2)") (class "Default")
      (node (ref "SAIDA_MOTOR_2") (pin "2") (pinfunction "2_2") (pintype "bidirectional"))
    )
    (net (code "69") (name "unconnected-(SAIDA_MOTOR_3-Pad2)") (class "Default")
      (node (ref "SAIDA_MOTOR_3") (pin "2") (pinfunction "2_2") (pintype "bidirectional"))
    )
    (net (code "70") (name "unconnected-(SAIDA_MOTOR_4-Pad2)") (class "Default")
      (node (ref "SAIDA_MOTOR_4") (pin "2") (pinfunction "2_2") (pintype "bidirectional"))
    )
  )
)
